# BoardC.net
KiCad netlist of a schematic drawn in Altium Designer
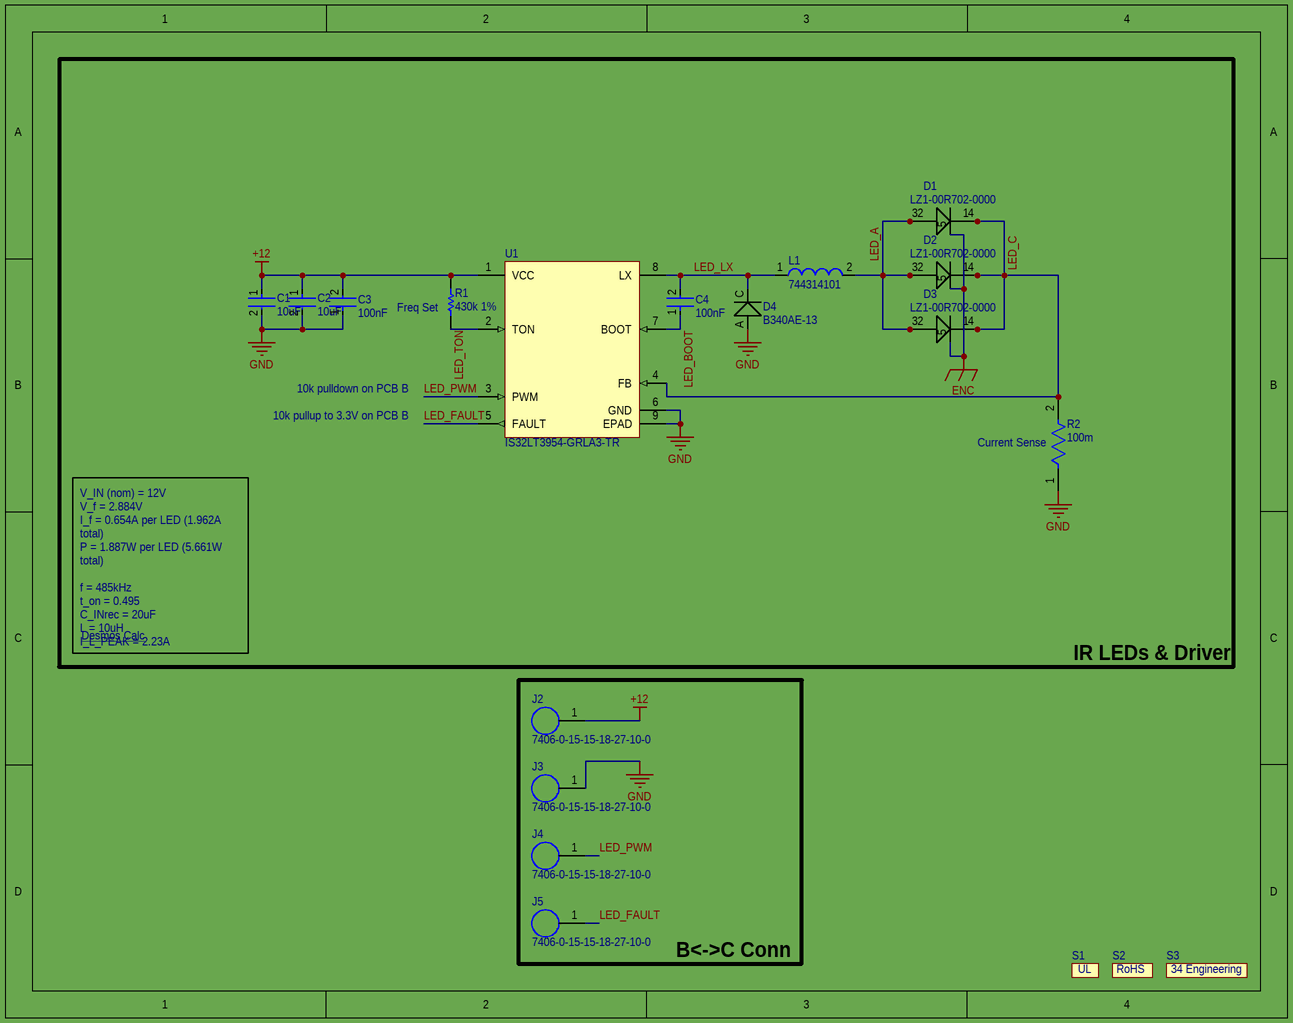
[diagram p0: BoardC.SchDoc]

(export (version "E")
  (design (tool "Eeschema 10.0.6"))
  (components
    (comp (ref "C1")
      (value "10uF")
      (footprint "FP-GRM188-0_2-MFG")
      (description "Chip Multilayer Ceramic Capacitors for General Purpose, 0603, 10uF, X5R, 15%, 20%, 25V")
      (fields (field (name "TOLERANCE") "20%") (field (name "VOLTAGE") "25V"))
      (libsource (lib "Altium Content Vault") (part "11868f565c42a9108669ba33697ecf6"))
    )
    (comp (ref "C2")
      (value "10uF")
      (footprint "FP-GRM188-0_2-MFG")
      (description "Chip Multilayer Ceramic Capacitors for General Purpose, 0603, 10uF, X5R, 15%, 20%, 25V")
      (fields (field (name "TOLERANCE") "20%") (field (name "VOLTAGE") "25V"))
      (libsource (lib "Altium Content Vault") (part "11868f565c42a9108669ba33697ecf6"))
    )
    (comp (ref "C3")
      (value "100nF")
      (footprint "FP-CGA3E-0_3-0_1-IPC_C")
      (description "Cap Ceramic 100nF 50V X7R 10% Pad SMD 0603 +125°C Automotive T/R")
      (fields (field (name "TOLERANCE") "10%") (field (name "VOLTAGE") "50V"))
      (libsource (lib "Altium Content Vault") (part "b4654b650e69147ec39a6b967a45e02"))
    )
    (comp (ref "C4")
      (value "100nF")
      (footprint "FP-CGA3E-0_3-0_1-IPC_C")
      (description "Cap Ceramic 100nF 50V X7R 10% Pad SMD 0603 +125°C Automotive T/R")
      (fields (field (name "TOLERANCE") "10%") (field (name "VOLTAGE") "50V"))
      (libsource (lib "Altium Content Vault") (part "b4654b650e69147ec39a6b967a45e02"))
    )
    (comp (ref "D1")
      (value "LZ1-00R702-0000")
      (footprint "LZ1-00R702-0000")
      (description "IR Emitter 940nm 1600mW 1200mA 3.05V 4-Pin CSMD T/R")
      (fields (field (name "MANUFACTURER") "LED Engin"))
      (libsource (lib "Virtex") (part "LZ1-00R702-0000"))
    )
    (comp (ref "D2")
      (value "LZ1-00R702-0000")
      (footprint "LZ1-00R702-0000")
      (description "IR Emitter 940nm 1600mW 1200mA 3.05V 4-Pin CSMD T/R")
      (fields (field (name "MANUFACTURER") "LED Engin"))
      (libsource (lib "Virtex") (part "LZ1-00R702-0000"))
    )
    (comp (ref "D3")
      (value "LZ1-00R702-0000")
      (footprint "LZ1-00R702-0000")
      (description "IR Emitter 940nm 1600mW 1200mA 3.05V 4-Pin CSMD T/R")
      (fields (field (name "MANUFACTURER") "LED Engin"))
      (libsource (lib "Virtex") (part "LZ1-00R702-0000"))
    )
    (comp (ref "D4")
      (value "B340AE-13")
      (footprint "B340AE-13")
      (description "Rectifier Diode Schottky 40V 3A 2-Pin SMA T/R")
      (fields (field (name "MANUFACTURER") "Diodes"))
      (libsource (lib "Virtex") (part "B340AE-13"))
    )
    (comp (ref "J2")
      (value "7406-0-15-15-18-27-10-0")
      (footprint "7406-0-15-15-18-27-10-0")
      (description "3.05 mm PCB Through Hole Pin Receptacle for (0.94 to 1.09 mm Pin) w/ No Tail")
      (fields (field (name "MANUFACTURER") "Mill-Max"))
      (libsource (lib "Virtex") (part "7406-0-15-15-18-27-10-0"))
    )
    (comp (ref "J3")
      (value "7406-0-15-15-18-27-10-0")
      (footprint "7406-0-15-15-18-27-10-0")
      (description "3.05 mm PCB Through Hole Pin Receptacle for (0.94 to 1.09 mm Pin) w/ No Tail")
      (fields (field (name "MANUFACTURER") "Mill-Max"))
      (libsource (lib "Virtex") (part "7406-0-15-15-18-27-10-0"))
    )
    (comp (ref "J4")
      (value "7406-0-15-15-18-27-10-0")
      (footprint "7406-0-15-15-18-27-10-0")
      (description "3.05 mm PCB Through Hole Pin Receptacle for (0.94 to 1.09 mm Pin) w/ No Tail")
      (fields (field (name "MANUFACTURER") "Mill-Max"))
      (libsource (lib "Virtex") (part "7406-0-15-15-18-27-10-0"))
    )
    (comp (ref "J5")
      (value "7406-0-15-15-18-27-10-0")
      (footprint "7406-0-15-15-18-27-10-0")
      (description "3.05 mm PCB Through Hole Pin Receptacle for (0.94 to 1.09 mm Pin) w/ No Tail")
      (fields (field (name "MANUFACTURER") "Mill-Max"))
      (libsource (lib "Virtex") (part "7406-0-15-15-18-27-10-0"))
    )
    (comp (ref "L1")
      (value "744314101")
      (footprint "WE-HCI-7050")
      (description "SMD Flat Wire High Current Inductor WE-HCI, L=10.0 µH")
      (libsource (lib "Altium Content Vault") (part "PAS-IND-INDUCTOR-2"))
    )
    (comp (ref "R1")
      (value "430k 1%")
      (footprint "RESC1608X55X30LL15T15")
      (fields (field (name "MANUFACTURER") "Panasonic") (field (name "PART NUMBER") "ERJ-3EKF4303V"))
      (libsource (lib "Altium Content Vault") (part "RES"))
    )
    (comp (ref "R2")
      (value "100m")
      (footprint "FP-ERJ6D-MFG")
      (description "RES 0.1 OHM 1% 1/2W 0805")
      (fields (field (name "TOLERANCE") "1%"))
      (libsource (lib "Altium Content Vault") (part "1029c3af85768c4190bb7ad29bc67b5"))
    )
    (comp (ref "S1") (value "~") (footprint "UL") (libsource (lib "Virtex") (part "UL")))
    (comp (ref "S2") (value "~") (footprint "RoHS") (libsource (lib "Virtex") (part "RoHS")))
    (comp (ref "S3")
      (value "~")
      (footprint "34EngineeringLogo")
      (description "34 Engineering Silkscreen Logo")
      (libsource (lib "Virtex") (part "34EngineeringLogo"))
    )
    (comp (ref "U1")
      (value "IS32LT3954-GRLA3-TR")
      (footprint "IS32LT3954-GRLA3-TR")
      (description "3.0A Dimmable Buck Switching Regulator with Fault Reporting, Spread Spectrum, SOP-8-EP")
      (fields (field (name "MANUFACTURER") "ISSI"))
      (libsource (lib "Virtex") (part "IS32LT3954-GRLA3-TR"))
    )
  )
  (nets
    (net (code "1") (name "+12") (class "Default")
      (node (ref "C1") (pin "1") (pinfunction "1_1") (pintype "passive"))
      (node (ref "C2") (pin "1") (pinfunction "1_1") (pintype "passive"))
      (node (ref "C3") (pin "2") (pinfunction "2_2") (pintype "passive"))
      (node (ref "J2") (pin "1") (pintype "passive"))
      (node (ref "R1") (pin "2") (pinfunction "2_2") (pintype "passive"))
      (node (ref "U1") (pin "1") (pinfunction "VCC_1") (pintype "power_in"))
    )
    (net (code "2") (name "/LED_A") (class "Default")
      (node (ref "D1") (pin "2") (pintype "power_in"))
      (node (ref "D1") (pin "3") (pintype "power_in"))
      (node (ref "D2") (pin "2") (pintype "power_in"))
      (node (ref "D2") (pin "3") (pintype "power_in"))
      (node (ref "D3") (pin "2") (pintype "power_in"))
      (node (ref "D3") (pin "3") (pintype "power_in"))
      (node (ref "L1") (pin "2") (pinfunction "2_2") (pintype "passive"))
    )
    (net (code "3") (name "/LED_BOOT") (class "Default")
      (node (ref "C4") (pin "1") (pinfunction "1_1") (pintype "passive"))
      (node (ref "U1") (pin "7") (pinfunction "BOOT_7") (pintype "input"))
    )
    (net (code "4") (name "/LED_C") (class "Default")
      (node (ref "D1") (pin "1") (pintype "power_in"))
      (node (ref "D1") (pin "4") (pintype "power_in"))
      (node (ref "D2") (pin "1") (pintype "power_in"))
      (node (ref "D2") (pin "4") (pintype "power_in"))
      (node (ref "D3") (pin "1") (pintype "power_in"))
      (node (ref "D3") (pin "4") (pintype "power_in"))
      (node (ref "R2") (pin "2") (pinfunction "2_2") (pintype "passive"))
      (node (ref "U1") (pin "4") (pinfunction "FB_4") (pintype "input"))
    )
    (net (code "5") (name "/LED_FAULT") (class "Default")
      (node (ref "J5") (pin "1") (pintype "passive"))
      (node (ref "U1") (pin "5") (pinfunction "FAULT_5") (pintype "output"))
    )
    (net (code "6") (name "/LED_LX") (class "Default")
      (node (ref "C4") (pin "2") (pinfunction "2_2") (pintype "passive"))
      (node (ref "D4") (pin "C") (pintype "power_in"))
      (node (ref "L1") (pin "1") (pinfunction "1_1") (pintype "passive"))
      (node (ref "U1") (pin "8") (pinfunction "LX_8") (pintype "power_in"))
    )
    (net (code "7") (name "/LED_PWM") (class "Default")
      (node (ref "J4") (pin "1") (pintype "passive"))
      (node (ref "U1") (pin "3") (pinfunction "PWM_3") (pintype "input"))
    )
    (net (code "8") (name "/LED_TON") (class "Default")
      (node (ref "R1") (pin "1") (pinfunction "1_1") (pintype "passive"))
      (node (ref "U1") (pin "2") (pinfunction "TON_2") (pintype "input"))
    )
    (net (code "9") (name "ENC") (class "Default")
      (node (ref "D1") (pin "5") (pintype "power_in"))
      (node (ref "D2") (pin "5") (pintype "power_in"))
      (node (ref "D3") (pin "5") (pintype "power_in"))
    )
    (net (code "10") (name "GND") (class "Default")
      (node (ref "C1") (pin "2") (pinfunction "2_2") (pintype "passive"))
      (node (ref "C2") (pin "2") (pinfunction "2_2") (pintype "passive"))
      (node (ref "C3") (pin "1") (pinfunction "1_1") (pintype "passive"))
      (node (ref "D4") (pin "A") (pintype "power_in"))
      (node (ref "J3") (pin "1") (pintype "passive"))
      (node (ref "R2") (pin "1") (pinfunction "1_1") (pintype "passive"))
      (node (ref "U1") (pin "6") (pinfunction "GND_6") (pintype "power_in"))
      (node (ref "U1") (pin "9") (pinfunction "EPAD_9") (pintype "power_in"))
    )
  )
)
